# FPGA.net
KiCad netlist of a schematic drawn in Altium Designer
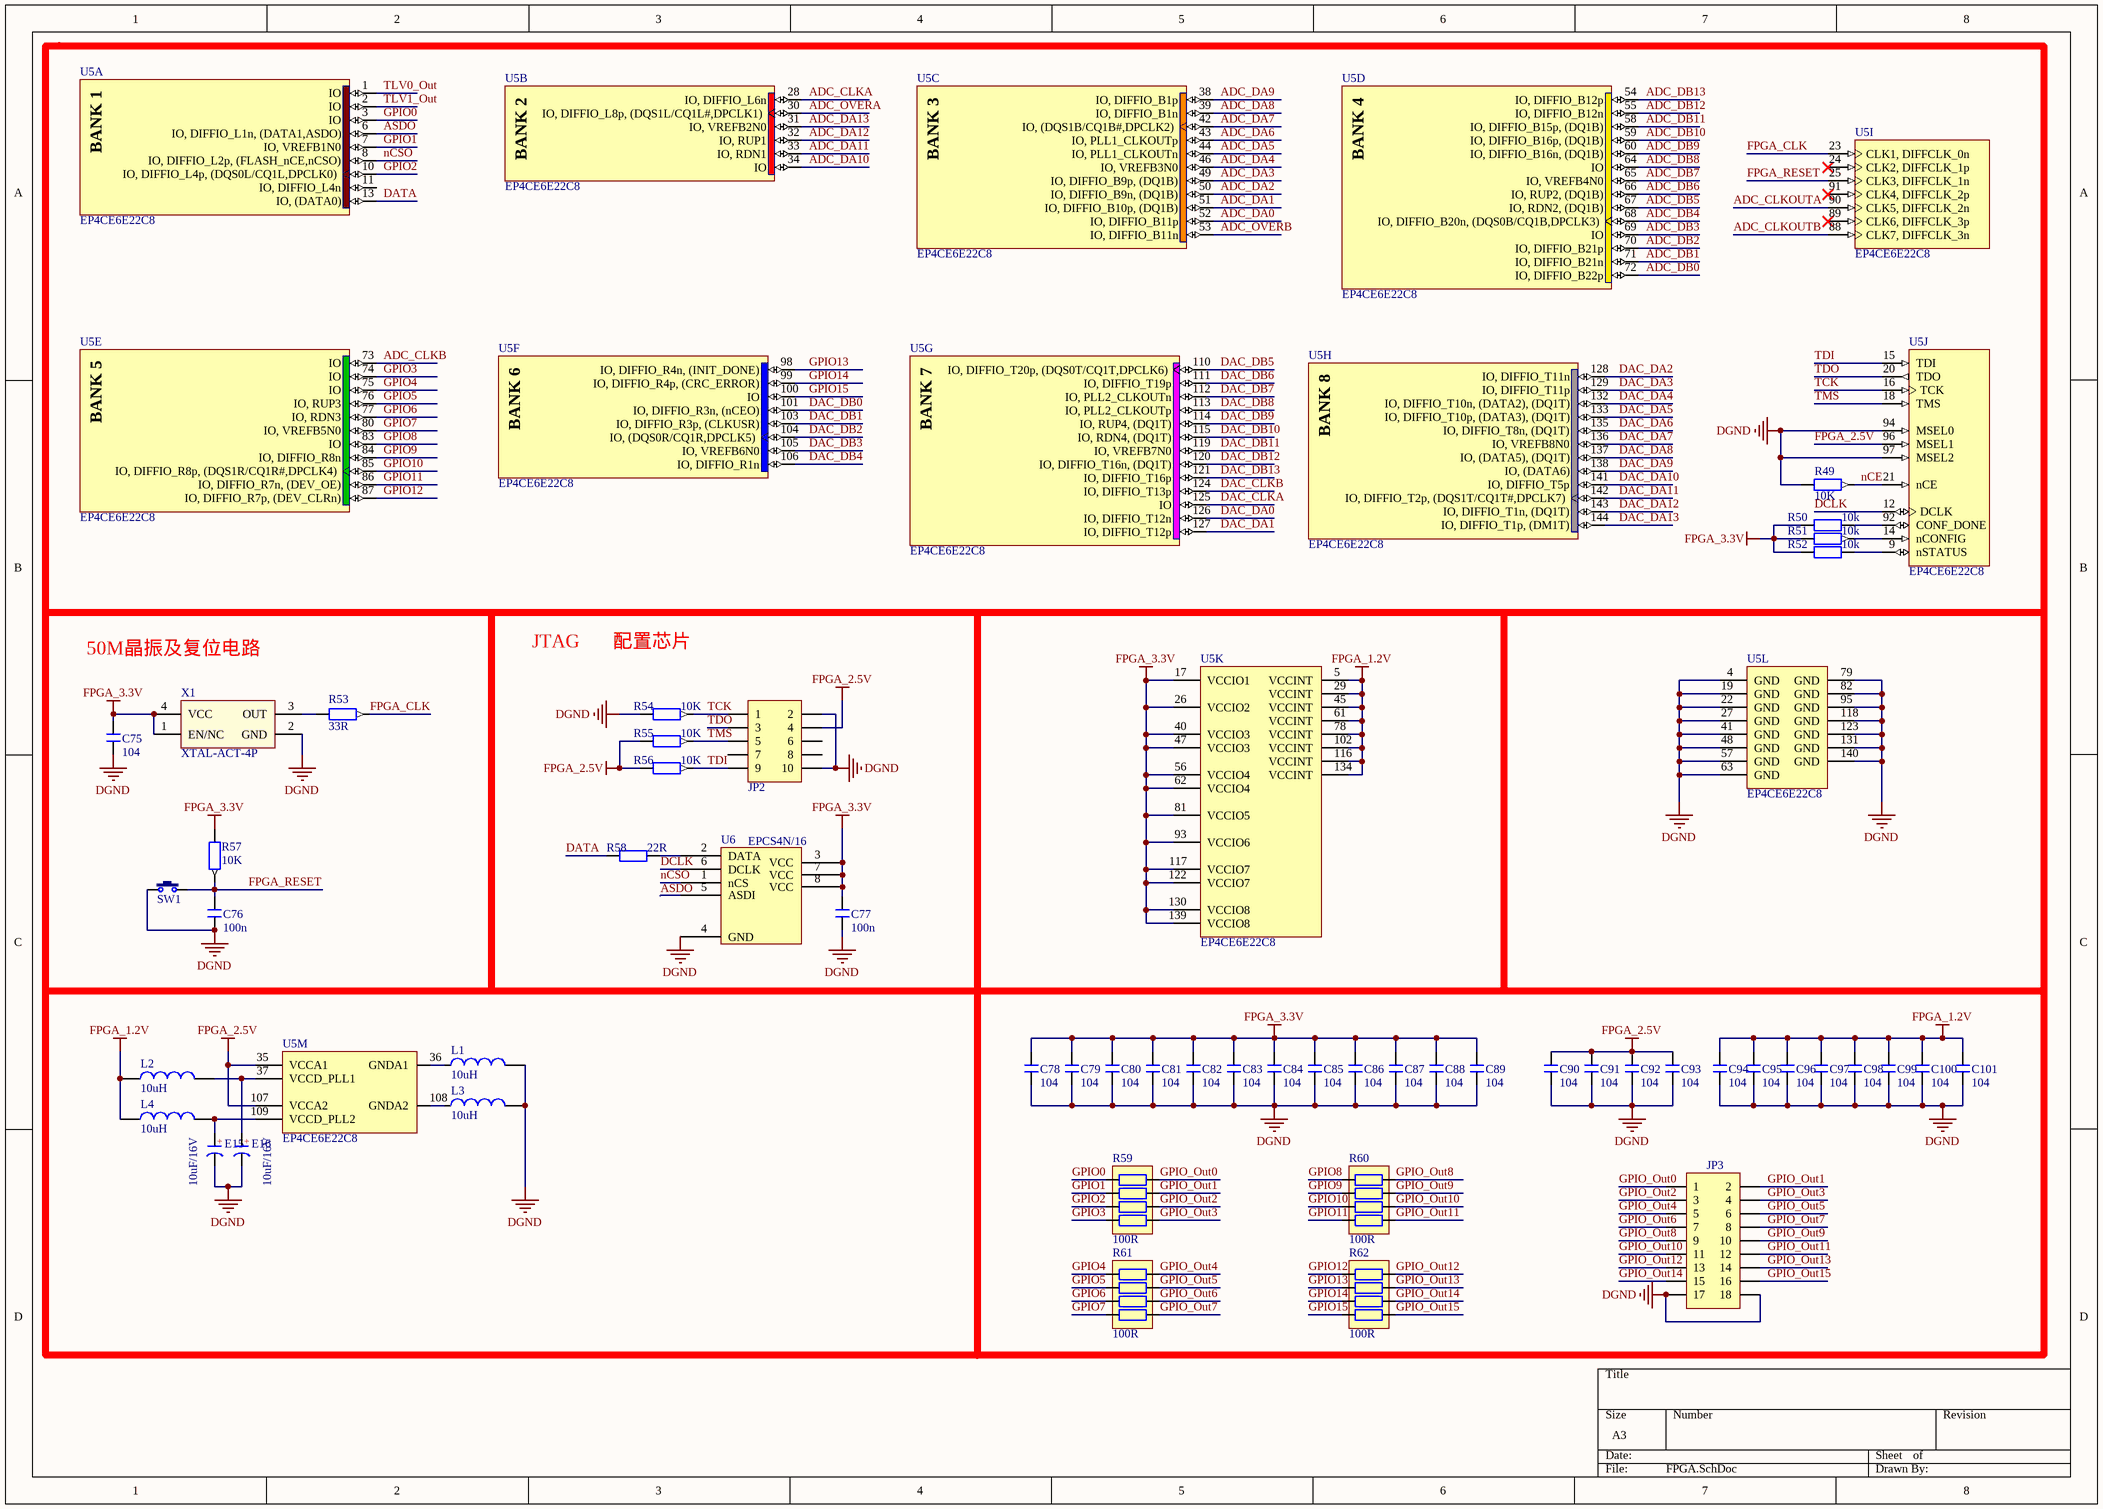
[diagram p0: FPGA.SchDoc]

(export (version "E")
  (design (tool "Eeschema 10.0.6"))
  (components
    (comp (ref "C75")
      (value "104")
      (footprint "C 0805_M")
      (description "无极性贴片电容")
      (fields (field (name "版权归属") "源创客"))
      (libsource (lib "3.1   - 电阻-电容-电感") (part "C"))
    )
    (comp (ref "C76")
      (value "100n")
      (footprint "C 0805_M")
      (description "无极性贴片电容")
      (fields (field (name "版权归属") "源创客"))
      (libsource (lib "3.1   - 电阻-电容-电感") (part "C"))
    )
    (comp (ref "C77")
      (value "100n")
      (footprint "C 0805_M")
      (description "无极性贴片电容")
      (fields (field (name "版权归属") "源创客"))
      (libsource (lib "3.1   - 电阻-电容-电感") (part "C"))
    )
    (comp (ref "C78")
      (value "104")
      (footprint "C 0805_M")
      (description "无极性贴片电容")
      (fields (field (name "版权归属") "源创客"))
      (libsource (lib "3.1   - 电阻-电容-电感") (part "C"))
    )
    (comp (ref "C79")
      (value "104")
      (footprint "C 0805_M")
      (description "无极性贴片电容")
      (fields (field (name "版权归属") "源创客"))
      (libsource (lib "3.1   - 电阻-电容-电感") (part "C"))
    )
    (comp (ref "C80")
      (value "104")
      (footprint "C 0805_M")
      (description "无极性贴片电容")
      (fields (field (name "版权归属") "源创客"))
      (libsource (lib "3.1   - 电阻-电容-电感") (part "C"))
    )
    (comp (ref "C81")
      (value "104")
      (footprint "C 0805_M")
      (description "无极性贴片电容")
      (fields (field (name "版权归属") "源创客"))
      (libsource (lib "3.1   - 电阻-电容-电感") (part "C"))
    )
    (comp (ref "C82")
      (value "104")
      (footprint "C 0805_M")
      (description "无极性贴片电容")
      (fields (field (name "版权归属") "源创客"))
      (libsource (lib "3.1   - 电阻-电容-电感") (part "C"))
    )
    (comp (ref "C83")
      (value "104")
      (footprint "C 0805_M")
      (description "无极性贴片电容")
      (fields (field (name "版权归属") "源创客"))
      (libsource (lib "3.1   - 电阻-电容-电感") (part "C"))
    )
    (comp (ref "C84")
      (value "104")
      (footprint "C 0805_M")
      (description "无极性贴片电容")
      (fields (field (name "版权归属") "源创客"))
      (libsource (lib "3.1   - 电阻-电容-电感") (part "C"))
    )
    (comp (ref "C85")
      (value "104")
      (footprint "C 0805_M")
      (description "无极性贴片电容")
      (fields (field (name "版权归属") "源创客"))
      (libsource (lib "3.1   - 电阻-电容-电感") (part "C"))
    )
    (comp (ref "C86")
      (value "104")
      (footprint "C 0805_M")
      (description "无极性贴片电容")
      (fields (field (name "版权归属") "源创客"))
      (libsource (lib "3.1   - 电阻-电容-电感") (part "C"))
    )
    (comp (ref "C87")
      (value "104")
      (footprint "C 0805_M")
      (description "无极性贴片电容")
      (fields (field (name "版权归属") "源创客"))
      (libsource (lib "3.1   - 电阻-电容-电感") (part "C"))
    )
    (comp (ref "C88")
      (value "104")
      (footprint "C 0805_M")
      (description "无极性贴片电容")
      (fields (field (name "版权归属") "源创客"))
      (libsource (lib "3.1   - 电阻-电容-电感") (part "C"))
    )
    (comp (ref "C89")
      (value "104")
      (footprint "C 0805_M")
      (description "无极性贴片电容")
      (fields (field (name "版权归属") "源创客"))
      (libsource (lib "3.1   - 电阻-电容-电感") (part "C"))
    )
    (comp (ref "C90")
      (value "104")
      (footprint "C 0805_M")
      (description "无极性贴片电容")
      (fields (field (name "版权归属") "源创客"))
      (libsource (lib "3.1   - 电阻-电容-电感") (part "C"))
    )
    (comp (ref "C91")
      (value "104")
      (footprint "C 0805_M")
      (description "无极性贴片电容")
      (fields (field (name "版权归属") "源创客"))
      (libsource (lib "3.1   - 电阻-电容-电感") (part "C"))
    )
    (comp (ref "C92")
      (value "104")
      (footprint "C 0805_M")
      (description "无极性贴片电容")
      (fields (field (name "版权归属") "源创客"))
      (libsource (lib "3.1   - 电阻-电容-电感") (part "C"))
    )
    (comp (ref "C93")
      (value "104")
      (footprint "C 0805_M")
      (description "无极性贴片电容")
      (fields (field (name "版权归属") "源创客"))
      (libsource (lib "3.1   - 电阻-电容-电感") (part "C"))
    )
    (comp (ref "C94")
      (value "104")
      (footprint "C 0805_M")
      (description "无极性贴片电容")
      (fields (field (name "版权归属") "源创客"))
      (libsource (lib "3.1   - 电阻-电容-电感") (part "C"))
    )
    (comp (ref "C95")
      (value "104")
      (footprint "C 0805_M")
      (description "无极性贴片电容")
      (fields (field (name "版权归属") "源创客"))
      (libsource (lib "3.1   - 电阻-电容-电感") (part "C"))
    )
    (comp (ref "C96")
      (value "104")
      (footprint "C 0805_M")
      (description "无极性贴片电容")
      (fields (field (name "版权归属") "源创客"))
      (libsource (lib "3.1   - 电阻-电容-电感") (part "C"))
    )
    (comp (ref "C97")
      (value "104")
      (footprint "C 0805_M")
      (description "无极性贴片电容")
      (fields (field (name "版权归属") "源创客"))
      (libsource (lib "3.1   - 电阻-电容-电感") (part "C"))
    )
    (comp (ref "C98")
      (value "104")
      (footprint "C 0805_M")
      (description "无极性贴片电容")
      (fields (field (name "版权归属") "源创客"))
      (libsource (lib "3.1   - 电阻-电容-电感") (part "C"))
    )
    (comp (ref "C99")
      (value "104")
      (footprint "C 0805_M")
      (description "无极性贴片电容")
      (fields (field (name "版权归属") "源创客"))
      (libsource (lib "3.1   - 电阻-电容-电感") (part "C"))
    )
    (comp (ref "C100")
      (value "104")
      (footprint "C 0805_M")
      (description "无极性贴片电容")
      (fields (field (name "版权归属") "源创客"))
      (libsource (lib "3.1   - 电阻-电容-电感") (part "C"))
    )
    (comp (ref "C101")
      (value "104")
      (footprint "C 0805_M")
      (description "无极性贴片电容")
      (fields (field (name "版权归属") "源创客"))
      (libsource (lib "3.1   - 电阻-电容-电感") (part "C"))
    )
    (comp (ref "E15")
      (value "10uF/16V")
      (footprint "C 1210_M")
      (description "直插电解电容")
      (fields (field (name "版权归属") "源创客"))
      (libsource (lib "3.1   - 电阻-电容-电感") (part "C-CAP"))
    )
    (comp (ref "E16")
      (value "10uF/16V")
      (footprint "C 1210_M")
      (description "直插电解电容")
      (fields (field (name "版权归属") "源创客"))
      (libsource (lib "3.1   - 电阻-电容-电感") (part "C-CAP"))
    )
    (comp (ref "JP2")
      (value "Header 5X2")
      (footprint "IDC2.54-LI-2x5P")
      (description "5*2P接插件")
      (fields (field (name "版权归属") "源创客"))
      (libsource (lib "4.5   - 接插件-脚距2.54") (part "Header 5X2"))
    )
    (comp (ref "JP3")
      (value "Header 9X2")
      (footprint "HDR2.54-LI-2x9P")
      (description "9*2P接插件")
      (fields (field (name "版权归属") "源创客"))
      (libsource (lib "4.5   - 接插件-脚距2.54") (part "Header 9X2"))
    )
    (comp (ref "L1")
      (value "10uH")
      (footprint "L 0805")
      (description "小功率贴片电感")
      (fields (field (name "版权归属") "源创客"))
      (libsource (lib "3.1   - 电阻-电容-电感") (part "L"))
    )
    (comp (ref "L2")
      (value "10uH")
      (footprint "L 0805")
      (description "小功率贴片电感")
      (fields (field (name "版权归属") "源创客"))
      (libsource (lib "3.1   - 电阻-电容-电感") (part "L"))
    )
    (comp (ref "L3")
      (value "10uH")
      (footprint "L 0805")
      (description "小功率贴片电感")
      (fields (field (name "版权归属") "源创客"))
      (libsource (lib "3.1   - 电阻-电容-电感") (part "L"))
    )
    (comp (ref "L4")
      (value "10uH")
      (footprint "L 0805")
      (description "小功率贴片电感")
      (fields (field (name "版权归属") "源创客"))
      (libsource (lib "3.1   - 电阻-电容-电感") (part "L"))
    )
    (comp (ref "R49")
      (value "10K")
      (footprint "R 0805_M")
      (description "Resistor")
      (fields (field (name "PUBLISHER") "Altium Limited"))
      (libsource (lib "Miscellaneous Devices") (part "Res2"))
    )
    (comp (ref "R50")
      (value "10k")
      (footprint "R 0805_M")
      (description "贴片电阻")
      (fields (field (name "版权归属") "源创客"))
      (libsource (lib "3.1   - 电阻-电容-电感") (part "R"))
    )
    (comp (ref "R51")
      (value "10k")
      (footprint "R 0805_M")
      (description "贴片电阻")
      (fields (field (name "版权归属") "源创客"))
      (libsource (lib "3.1   - 电阻-电容-电感") (part "R"))
    )
    (comp (ref "R52")
      (value "10k")
      (footprint "R 0805_M")
      (description "贴片电阻")
      (fields (field (name "版权归属") "源创客"))
      (libsource (lib "3.1   - 电阻-电容-电感") (part "R"))
    )
    (comp (ref "R53")
      (value "33R")
      (footprint "R 0805_M")
      (description "贴片电阻")
      (fields (field (name "版权归属") "源创客"))
      (libsource (lib "3.1   - 电阻-电容-电感") (part "R"))
    )
    (comp (ref "R54")
      (value "10K")
      (footprint "R 0805_M")
      (description "贴片电阻")
      (fields (field (name "版权归属") "源创客"))
      (libsource (lib "3.1   - 电阻-电容-电感") (part "R"))
    )
    (comp (ref "R55")
      (value "10K")
      (footprint "R 0805_M")
      (description "贴片电阻")
      (fields (field (name "版权归属") "源创客"))
      (libsource (lib "3.1   - 电阻-电容-电感") (part "R"))
    )
    (comp (ref "R56")
      (value "10K")
      (footprint "R 0805_M")
      (description "贴片电阻")
      (fields (field (name "版权归属") "源创客"))
      (libsource (lib "3.1   - 电阻-电容-电感") (part "R"))
    )
    (comp (ref "R57")
      (value "10K")
      (footprint "R 0805_M")
      (description "贴片电阻")
      (fields (field (name "版权归属") "源创客"))
      (libsource (lib "3.1   - 电阻-电容-电感") (part "R"))
    )
    (comp (ref "R58")
      (value "22R")
      (footprint "R 0805_M")
      (description "贴片电阻")
      (fields (field (name "版权归属") "源创客"))
      (libsource (lib "3.1   - 电阻-电容-电感") (part "R"))
    )
    (comp (ref "R59")
      (value "100R")
      (footprint "RCA-8P4R-0603")
      (description "贴片网络排阻")
      (fields (field (name "版权归属") "源创客"))
      (libsource (lib "") (part "R-8P4R_1"))
    )
    (comp (ref "R60")
      (value "100R")
      (footprint "RCA-8P4R-0603")
      (description "贴片网络排阻")
      (fields (field (name "版权归属") "源创客"))
      (libsource (lib "") (part "R-8P4R_1"))
    )
    (comp (ref "R61")
      (value "100R")
      (footprint "RCA-8P4R-0603")
      (description "贴片网络排阻")
      (fields (field (name "版权归属") "源创客"))
      (libsource (lib "3.1   - 电阻-电容-电感") (part "R-8P4R"))
    )
    (comp (ref "R62")
      (value "100R")
      (footprint "RCA-8P4R-0603")
      (description "贴片网络排阻")
      (fields (field (name "版权归属") "源创客"))
      (libsource (lib "") (part "R-8P4R_1"))
    )
    (comp (ref "SW1")
      (value "3x6x5")
      (footprint "TSW SMD-3*6*2.5")
      (description "3x6轻触开关")
      (fields (field (name "版权归属") "源创客"))
      (libsource (lib "5.1   - 按键-开关") (part "TSW 3x6"))
    )
    (comp (ref "U5")
      (value "EP4CE6E22C8")
      (footprint "EQFP144_M")
      (description "Cyclone IV Family FPGA, 2V Core, 91 I/O Pins, 2 PLLs, 144-Pin QFP, Speed Grade 8, Commercial Grade")
      (fields (field (name "PUBLISHER") "Altium Limited"))
      (libsource (lib "Altera Cyclone IV E") (part "EP4CE6E22C8"))
    )
    (comp (ref "U6") (value "EPCS4N/16") (footprint "SOP8_M") (libsource (lib "M4") (part "EPCS1SI8")))
    (comp (ref "X1")
      (value "XTAL-ACT-4P")
      (footprint "OSC 7050-4P")
      (description "4脚有源晶振")
      (libsource (lib "晶振") (part "XTAL-ACT-4P"))
    )
  )
  (nets
    (net (code "1") (name "/ADC_CLKA") (class "Default")
      (node (ref "U5") (pin "28") (pinfunction "IO,_DIFFIO_L6n_28") (pintype "bidirectional"))
    )
    (net (code "2") (name "/ADC_CLKB") (class "Default")
      (node (ref "U5") (pin "73") (pinfunction "IO_73") (pintype "bidirectional"))
    )
    (net (code "3") (name "/ADC_CLKOUTA") (class "Default")
      (node (ref "U5") (pin "90") (pinfunction "CLK5,_DIFFCLK_2n_90") (pintype "input"))
    )
    (net (code "4") (name "/ADC_CLKOUTB") (class "Default")
      (node (ref "U5") (pin "88") (pinfunction "CLK7,_DIFFCLK_3n_88") (pintype "input"))
    )
    (net (code "5") (name "/ADC_DA0") (class "Default")
      (node (ref "U5") (pin "52") (pinfunction "IO,_DIFFIO_B11p_52") (pintype "bidirectional"))
    )
    (net (code "6") (name "/ADC_DA1") (class "Default")
      (node (ref "U5") (pin "51") (pinfunction "IO,_DIFFIO_B10p,_(DQ1B)_51") (pintype "bidirectional"))
    )
    (net (code "7") (name "/ADC_DA2") (class "Default")
      (node (ref "U5") (pin "50") (pinfunction "IO,_DIFFIO_B9n,_(DQ1B)_50") (pintype "bidirectional"))
    )
    (net (code "8") (name "/ADC_DA3") (class "Default")
      (node (ref "U5") (pin "49") (pinfunction "IO,_DIFFIO_B9p,_(DQ1B)_49") (pintype "bidirectional"))
    )
    (net (code "9") (name "/ADC_DA4") (class "Default")
      (node (ref "U5") (pin "46") (pinfunction "IO,_VREFB3N0_46") (pintype "bidirectional"))
    )
    (net (code "10") (name "/ADC_DA5") (class "Default")
      (node (ref "U5") (pin "44") (pinfunction "IO,_PLL1_CLKOUTn_44") (pintype "bidirectional"))
    )
    (net (code "11") (name "/ADC_DA6") (class "Default")
      (node (ref "U5") (pin "43") (pinfunction "IO,_PLL1_CLKOUTp_43") (pintype "bidirectional"))
    )
    (net (code "12") (name "/ADC_DA7") (class "Default")
      (node (ref "U5") (pin "42") (pinfunction "IO,_(DQS1B/CQ1B#,DPCLK2)_42") (pintype "bidirectional"))
    )
    (net (code "13") (name "/ADC_DA8") (class "Default")
      (node (ref "U5") (pin "39") (pinfunction "IO,_DIFFIO_B1n_39") (pintype "bidirectional"))
    )
    (net (code "14") (name "/ADC_DA9") (class "Default")
      (node (ref "U5") (pin "38") (pinfunction "IO,_DIFFIO_B1p_38") (pintype "bidirectional"))
    )
    (net (code "15") (name "/ADC_DA10") (class "Default")
      (node (ref "U5") (pin "34") (pinfunction "IO_34") (pintype "bidirectional"))
    )
    (net (code "16") (name "/ADC_DA11") (class "Default")
      (node (ref "U5") (pin "33") (pinfunction "IO,_RDN1_33") (pintype "bidirectional"))
    )
    (net (code "17") (name "/ADC_DA12") (class "Default")
      (node (ref "U5") (pin "32") (pinfunction "IO,_RUP1_32") (pintype "bidirectional"))
    )
    (net (code "18") (name "/ADC_DA13") (class "Default")
      (node (ref "U5") (pin "31") (pinfunction "IO,_VREFB2N0_31") (pintype "bidirectional"))
    )
    (net (code "19") (name "/ADC_DB0") (class "Default")
      (node (ref "U5") (pin "72") (pinfunction "IO,_DIFFIO_B22p_72") (pintype "bidirectional"))
    )
    (net (code "20") (name "/ADC_DB1") (class "Default")
      (node (ref "U5") (pin "71") (pinfunction "IO,_DIFFIO_B21n_71") (pintype "bidirectional"))
    )
    (net (code "21") (name "/ADC_DB2") (class "Default")
      (node (ref "U5") (pin "70") (pinfunction "IO,_DIFFIO_B21p_70") (pintype "bidirectional"))
    )
    (net (code "22") (name "/ADC_DB3") (class "Default")
      (node (ref "U5") (pin "69") (pinfunction "IO_69") (pintype "bidirectional"))
    )
    (net (code "23") (name "/ADC_DB4") (class "Default")
      (node (ref "U5") (pin "68") (pinfunction "IO,_DIFFIO_B20n,_(DQS0B/CQ1B,DPCLK3)_68") (pintype "bidirectional"))
    )
    (net (code "24") (name "/ADC_DB5") (class "Default")
      (node (ref "U5") (pin "67") (pinfunction "IO,_RDN2,_(DQ1B)_67") (pintype "bidirectional"))
    )
    (net (code "25") (name "/ADC_DB6") (class "Default")
      (node (ref "U5") (pin "66") (pinfunction "IO,_RUP2,_(DQ1B)_66") (pintype "bidirectional"))
    )
    (net (code "26") (name "/ADC_DB7") (class "Default")
      (node (ref "U5") (pin "65") (pinfunction "IO,_VREFB4N0_65") (pintype "bidirectional"))
    )
    (net (code "27") (name "/ADC_DB8") (class "Default")
      (node (ref "U5") (pin "64") (pinfunction "IO_64") (pintype "bidirectional"))
    )
    (net (code "28") (name "/ADC_DB9") (class "Default")
      (node (ref "U5") (pin "60") (pinfunction "IO,_DIFFIO_B16n,_(DQ1B)_60") (pintype "bidirectional"))
    )
    (net (code "29") (name "/ADC_DB10") (class "Default")
      (node (ref "U5") (pin "59") (pinfunction "IO,_DIFFIO_B16p,_(DQ1B)_59") (pintype "bidirectional"))
    )
    (net (code "30") (name "/ADC_DB11") (class "Default")
      (node (ref "U5") (pin "58") (pinfunction "IO,_DIFFIO_B15p,_(DQ1B)_58") (pintype "bidirectional"))
    )
    (net (code "31") (name "/ADC_DB12") (class "Default")
      (node (ref "U5") (pin "55") (pinfunction "IO,_DIFFIO_B12n_55") (pintype "bidirectional"))
    )
    (net (code "32") (name "/ADC_DB13") (class "Default")
      (node (ref "U5") (pin "54") (pinfunction "IO,_DIFFIO_B12p_54") (pintype "bidirectional"))
    )
    (net (code "33") (name "/ADC_OVERA") (class "Default")
      (node (ref "U5") (pin "30") (pinfunction "IO,_DIFFIO_L8p,_(DQS1L/CQ1L#,DPCLK1)_30") (pintype "bidirectional"))
    )
    (net (code "34") (name "/ADC_OVERB") (class "Default")
      (node (ref "U5") (pin "53") (pinfunction "IO,_DIFFIO_B11n_53") (pintype "bidirectional"))
    )
    (net (code "35") (name "/ASDO") (class "Default")
      (node (ref "U5") (pin "6") (pinfunction "IO,_DIFFIO_L1n,_(DATA1,ASDO)_6") (pintype "bidirectional"))
      (node (ref "U6") (pin "5") (pinfunction "ASDI_5") (pintype "passive"))
    )
    (net (code "36") (name "/DAC_CLKA") (class "Default")
      (node (ref "U5") (pin "125") (pinfunction "IO_125") (pintype "bidirectional"))
    )
    (net (code "37") (name "/DAC_CLKB") (class "Default")
      (node (ref "U5") (pin "124") (pinfunction "IO,_DIFFIO_T13p_124") (pintype "bidirectional"))
    )
    (net (code "38") (name "/DAC_DA0") (class "Default")
      (node (ref "U5") (pin "126") (pinfunction "IO,_DIFFIO_T12n_126") (pintype "bidirectional"))
    )
    (net (code "39") (name "/DAC_DA1") (class "Default")
      (node (ref "U5") (pin "127") (pinfunction "IO,_DIFFIO_T12p_127") (pintype "bidirectional"))
    )
    (net (code "40") (name "/DAC_DA2") (class "Default")
      (node (ref "U5") (pin "128") (pinfunction "IO,_DIFFIO_T11n_128") (pintype "bidirectional"))
    )
    (net (code "41") (name "/DAC_DA3") (class "Default")
      (node (ref "U5") (pin "129") (pinfunction "IO,_DIFFIO_T11p_129") (pintype "bidirectional"))
    )
    (net (code "42") (name "/DAC_DA4") (class "Default")
      (node (ref "U5") (pin "132") (pinfunction "IO,_DIFFIO_T10n,_(DATA2),_(DQ1T)_132") (pintype "bidirectional"))
    )
    (net (code "43") (name "/DAC_DA5") (class "Default")
      (node (ref "U5") (pin "133") (pinfunction "IO,_DIFFIO_T10p,_(DATA3),_(DQ1T)_133") (pintype "bidirectional"))
    )
    (net (code "44") (name "/DAC_DA6") (class "Default")
      (node (ref "U5") (pin "135") (pinfunction "IO,_DIFFIO_T8n,_(DQ1T)_135") (pintype "bidirectional"))
    )
    (net (code "45") (name "/DAC_DA7") (class "Default")
      (node (ref "U5") (pin "136") (pinfunction "IO,_VREFB8N0_136") (pintype "bidirectional"))
    )
    (net (code "46") (name "/DAC_DA8") (class "Default")
      (node (ref "U5") (pin "137") (pinfunction "IO,_(DATA5),_(DQ1T)_137") (pintype "bidirectional"))
    )
    (net (code "47") (name "/DAC_DA9") (class "Default")
      (node (ref "U5") (pin "138") (pinfunction "IO,_(DATA6)_138") (pintype "bidirectional"))
    )
    (net (code "48") (name "/DAC_DA10") (class "Default")
      (node (ref "U5") (pin "141") (pinfunction "IO,_DIFFIO_T5p_141") (pintype "bidirectional"))
    )
    (net (code "49") (name "/DAC_DA11") (class "Default")
      (node (ref "U5") (pin "142") (pinfunction "IO,_DIFFIO_T2p,_(DQS1T/CQ1T#,DPCLK7)_142") (pintype "bidirectional"))
    )
    (net (code "50") (name "/DAC_DA12") (class "Default")
      (node (ref "U5") (pin "143") (pinfunction "IO,_DIFFIO_T1n,_(DQ1T)_143") (pintype "bidirectional"))
    )
    (net (code "51") (name "/DAC_DA13") (class "Default")
      (node (ref "U5") (pin "144") (pinfunction "IO,_DIFFIO_T1p,_(DM1T)_144") (pintype "bidirectional"))
    )
    (net (code "52") (name "/DAC_DB0") (class "Default")
      (node (ref "U5") (pin "101") (pinfunction "IO,_DIFFIO_R3n,_(nCEO)_101") (pintype "bidirectional"))
    )
    (net (code "53") (name "/DAC_DB1") (class "Default")
      (node (ref "U5") (pin "103") (pinfunction "IO,_DIFFIO_R3p,_(CLKUSR)_103") (pintype "bidirectional"))
    )
    (net (code "54") (name "/DAC_DB2") (class "Default")
      (node (ref "U5") (pin "104") (pinfunction "IO,_(DQS0R/CQ1R,DPCLK5)_104") (pintype "bidirectional"))
    )
    (net (code "55") (name "/DAC_DB3") (class "Default")
      (node (ref "U5") (pin "105") (pinfunction "IO,_VREFB6N0_105") (pintype "bidirectional"))
    )
    (net (code "56") (name "/DAC_DB4") (class "Default")
      (node (ref "U5") (pin "106") (pinfunction "IO,_DIFFIO_R1n_106") (pintype "bidirectional"))
    )
    (net (code "57") (name "/DAC_DB5") (class "Default")
      (node (ref "U5") (pin "110") (pinfunction "IO,_DIFFIO_T20p,_(DQS0T/CQ1T,DPCLK6)_110") (pintype "bidirectional"))
    )
    (net (code "58") (name "/DAC_DB6") (class "Default")
      (node (ref "U5") (pin "111") (pinfunction "IO,_DIFFIO_T19p_111") (pintype "bidirectional"))
    )
    (net (code "59") (name "/DAC_DB7") (class "Default")
      (node (ref "U5") (pin "112") (pinfunction "IO,_PLL2_CLKOUTn_112") (pintype "bidirectional"))
    )
    (net (code "60") (name "/DAC_DB8") (class "Default")
      (node (ref "U5") (pin "113") (pinfunction "IO,_PLL2_CLKOUTp_113") (pintype "bidirectional"))
    )
    (net (code "61") (name "/DAC_DB9") (class "Default")
      (node (ref "U5") (pin "114") (pinfunction "IO,_RUP4,_(DQ1T)_114") (pintype "bidirectional"))
    )
    (net (code "62") (name "/DAC_DB10") (class "Default")
      (node (ref "U5") (pin "115") (pinfunction "IO,_RDN4,_(DQ1T)_115") (pintype "bidirectional"))
    )
    (net (code "63") (name "/DAC_DB11") (class "Default")
      (node (ref "U5") (pin "119") (pinfunction "IO,_VREFB7N0_119") (pintype "bidirectional"))
    )
    (net (code "64") (name "/DAC_DB12") (class "Default")
      (node (ref "U5") (pin "120") (pinfunction "IO,_DIFFIO_T16n,_(DQ1T)_120") (pintype "bidirectional"))
    )
    (net (code "65") (name "/DAC_DB13") (class "Default")
      (node (ref "U5") (pin "121") (pinfunction "IO,_DIFFIO_T16p_121") (pintype "bidirectional"))
    )
    (net (code "66") (name "/DATA") (class "Default")
      (node (ref "R58") (pin "2") (pinfunction "2_2") (pintype "output"))
      (node (ref "U5") (pin "13") (pinfunction "IO,_(DATA0)_13") (pintype "bidirectional"))
    )
    (net (code "67") (name "/DCLK") (class "Default")
      (node (ref "U5") (pin "12") (pinfunction "DCLK_12") (pintype "bidirectional"))
      (node (ref "U6") (pin "6") (pinfunction "DCLK_6") (pintype "passive"))
    )
    (net (code "68") (name "/FPGA_CLK") (class "Default")
      (node (ref "R53") (pin "2") (pinfunction "2_2") (pintype "output"))
      (node (ref "U5") (pin "23") (pinfunction "CLK1,_DIFFCLK_0n_23") (pintype "input"))
    )
    (net (code "69") (name "/FPGA_RESET") (class "Default")
      (node (ref "C76") (pin "2") (pinfunction "2_2") (pintype "passive"))
      (node (ref "R57") (pin "1") (pinfunction "1_1") (pintype "passive"))
      (node (ref "SW1") (pin "2") (pinfunction "2_2") (pintype "passive"))
      (node (ref "U5") (pin "25") (pinfunction "CLK3,_DIFFCLK_1n_25") (pintype "input"))
    )
    (net (code "70") (name "/GPIO0") (class "Default")
      (node (ref "R59") (pin "8") (pinfunction "8_8") (pintype "passive"))
      (node (ref "U5") (pin "3") (pinfunction "IO_3") (pintype "bidirectional"))
    )
    (net (code "71") (name "/GPIO1") (class "Default")
      (node (ref "R59") (pin "7") (pinfunction "7_7") (pintype "passive"))
      (node (ref "U5") (pin "7") (pinfunction "IO,_VREFB1N0_7") (pintype "bidirectional"))
    )
    (net (code "72") (name "/GPIO2") (class "Default")
      (node (ref "R59") (pin "6") (pinfunction "6_6") (pintype "passive"))
      (node (ref "U5") (pin "10") (pinfunction "IO,_DIFFIO_L4p,_(DQS0L/CQ1L,DPCLK0)_10") (pintype "bidirectional"))
    )
    (net (code "73") (name "/GPIO3") (class "Default")
      (node (ref "R59") (pin "5") (pinfunction "5_5") (pintype "passive"))
      (node (ref "U5") (pin "74") (pinfunction "IO_74") (pintype "bidirectional"))
    )
    (net (code "74") (name "/GPIO4") (class "Default")
      (node (ref "R61") (pin "4") (pinfunction "4_4") (pintype "passive"))
      (node (ref "U5") (pin "75") (pinfunction "IO_75") (pintype "bidirectional"))
    )
    (net (code "75") (name "/GPIO5") (class "Default")
      (node (ref "R61") (pin "3") (pinfunction "3_3") (pintype "passive"))
      (node (ref "U5") (pin "76") (pinfunction "IO,_RUP3_76") (pintype "bidirectional"))
    )
    (net (code "76") (name "/GPIO6") (class "Default")
      (node (ref "R61") (pin "2") (pinfunction "2_2") (pintype "passive"))
      (node (ref "U5") (pin "77") (pinfunction "IO,_RDN3_77") (pintype "bidirectional"))
    )
    (net (code "77") (name "/GPIO7") (class "Default")
      (node (ref "R61") (pin "1") (pinfunction "1_1") (pintype "passive"))
      (node (ref "U5") (pin "80") (pinfunction "IO,_VREFB5N0_80") (pintype "bidirectional"))
    )
    (net (code "78") (name "/GPIO8") (class "Default")
      (node (ref "R60") (pin "8") (pinfunction "8_8") (pintype "passive"))
      (node (ref "U5") (pin "83") (pinfunction "IO_83") (pintype "bidirectional"))
    )
    (net (code "79") (name "/GPIO9") (class "Default")
      (node (ref "R60") (pin "7") (pinfunction "7_7") (pintype "passive"))
      (node (ref "U5") (pin "84") (pinfunction "IO,_DIFFIO_R8n_84") (pintype "bidirectional"))
    )
    (net (code "80") (name "/GPIO10") (class "Default")
      (node (ref "R60") (pin "6") (pinfunction "6_6") (pintype "passive"))
      (node (ref "U5") (pin "85") (pinfunction "IO,_DIFFIO_R8p,_(DQS1R/CQ1R#,DPCLK4)_85") (pintype "bidirectional"))
    )
    (net (code "81") (name "/GPIO11") (class "Default")
      (node (ref "R60") (pin "5") (pinfunction "5_5") (pintype "passive"))
      (node (ref "U5") (pin "86") (pinfunction "IO,_DIFFIO_R7n,_(DEV_OE)_86") (pintype "bidirectional"))
    )
    (net (code "82") (name "/GPIO12") (class "Default")
      (node (ref "R62") (pin "8") (pinfunction "8_8") (pintype "passive"))
      (node (ref "U5") (pin "87") (pinfunction "IO,_DIFFIO_R7p,_(DEV_CLRn)_87") (pintype "bidirectional"))
    )
    (net (code "83") (name "/GPIO13") (class "Default")
      (node (ref "R62") (pin "7") (pinfunction "7_7") (pintype "passive"))
      (node (ref "U5") (pin "98") (pinfunction "IO,_DIFFIO_R4n,_(INIT_DONE)_98") (pintype "bidirectional"))
    )
    (net (code "84") (name "/GPIO14") (class "Default")
      (node (ref "R62") (pin "6") (pinfunction "6_6") (pintype "passive"))
      (node (ref "U5") (pin "99") (pinfunction "IO,_DIFFIO_R4p,_(CRC_ERROR)_99") (pintype "bidirectional"))
    )
    (net (code "85") (name "/GPIO15") (class "Default")
      (node (ref "R62") (pin "5") (pinfunction "5_5") (pintype "passive"))
      (node (ref "U5") (pin "100") (pinfunction "IO_100") (pintype "bidirectional"))
    )
    (net (code "86") (name "/GPIO_Out0") (class "Default")
      (node (ref "JP3") (pin "1") (pinfunction "1_1") (pintype "passive"))
      (node (ref "R59") (pin "1") (pinfunction "1_1") (pintype "passive"))
    )
    (net (code "87") (name "/GPIO_Out1") (class "Default")
      (node (ref "JP3") (pin "2") (pinfunction "2_2") (pintype "passive"))
      (node (ref "R59") (pin "2") (pinfunction "2_2") (pintype "passive"))
    )
    (net (code "88") (name "/GPIO_Out2") (class "Default")
      (node (ref "JP3") (pin "3") (pinfunction "3_3") (pintype "passive"))
      (node (ref "R59") (pin "3") (pinfunction "3_3") (pintype "passive"))
    )
    (net (code "89") (name "/GPIO_Out3") (class "Default")
      (node (ref "JP3") (pin "4") (pinfunction "4_4") (pintype "passive"))
      (node (ref "R59") (pin "4") (pinfunction "4_4") (pintype "passive"))
    )
    (net (code "90") (name "/GPIO_Out4") (class "Default")
      (node (ref "JP3") (pin "5") (pinfunction "5_5") (pintype "passive"))
      (node (ref "R61") (pin "5") (pinfunction "5_5") (pintype "passive"))
    )
    (net (code "91") (name "/GPIO_Out5") (class "Default")
      (node (ref "JP3") (pin "6") (pinfunction "6_6") (pintype "passive"))
      (node (ref "R61") (pin "6") (pinfunction "6_6") (pintype "passive"))
    )
    (net (code "92") (name "/GPIO_Out6") (class "Default")
      (node (ref "JP3") (pin "7") (pinfunction "7_7") (pintype "passive"))
      (node (ref "R61") (pin "7") (pinfunction "7_7") (pintype "passive"))
    )
    (net (code "93") (name "/GPIO_Out7") (class "Default")
      (node (ref "JP3") (pin "8") (pinfunction "8_8") (pintype "passive"))
      (node (ref "R61") (pin "8") (pinfunction "8_8") (pintype "passive"))
    )
    (net (code "94") (name "/GPIO_Out8") (class "Default")
      (node (ref "JP3") (pin "9") (pinfunction "9_9") (pintype "passive"))
      (node (ref "R60") (pin "1") (pinfunction "1_1") (pintype "passive"))
    )
    (net (code "95") (name "/GPIO_Out9") (class "Default")
      (node (ref "JP3") (pin "10") (pinfunction "10_10") (pintype "passive"))
      (node (ref "R60") (pin "2") (pinfunction "2_2") (pintype "passive"))
    )
    (net (code "96") (name "/GPIO_Out10") (class "Default")
      (node (ref "JP3") (pin "11") (pinfunction "11_11") (pintype "passive"))
      (node (ref "R60") (pin "3") (pinfunction "3_3") (pintype "passive"))
    )
    (net (code "97") (name "/GPIO_Out11") (class "Default")
      (node (ref "JP3") (pin "12") (pinfunction "12_12") (pintype "passive"))
      (node (ref "R60") (pin "4") (pinfunction "4_4") (pintype "passive"))
    )
    (net (code "98") (name "/GPIO_Out12") (class "Default")
      (node (ref "JP3") (pin "13") (pinfunction "13_13") (pintype "passive"))
      (node (ref "R62") (pin "1") (pinfunction "1_1") (pintype "passive"))
    )
    (net (code "99") (name "/GPIO_Out13") (class "Default")
      (node (ref "JP3") (pin "14") (pinfunction "14_14") (pintype "passive"))
      (node (ref "R62") (pin "2") (pinfunction "2_2") (pintype "passive"))
    )
    (net (code "100") (name "/GPIO_Out14") (class "Default")
      (node (ref "JP3") (pin "15") (pinfunction "15_15") (pintype "passive"))
      (node (ref "R62") (pin "3") (pinfunction "3_3") (pintype "passive"))
    )
    (net (code "101") (name "/GPIO_Out15") (class "Default")
      (node (ref "JP3") (pin "16") (pinfunction "16_16") (pintype "passive"))
      (node (ref "R62") (pin "4") (pinfunction "4_4") (pintype "passive"))
    )
    (net (code "102") (name "/TCK") (class "Default")
      (node (ref "JP2") (pin "1") (pinfunction "1_1") (pintype "passive"))
      (node (ref "R54") (pin "1") (pinfunction "1_1") (pintype "passive"))
      (node (ref "U5") (pin "16") (pinfunction "TCK_16") (pintype "input"))
    )
    (net (code "103") (name "/TDI") (class "Default")
      (node (ref "JP2") (pin "9") (pinfunction "9_9") (pintype "passive"))
      (node (ref "R56") (pin "1") (pinfunction "1_1") (pintype "passive"))
      (node (ref "U5") (pin "15") (pinfunction "TDI_15") (pintype "input"))
    )
    (net (code "104") (name "/TDO") (class "Default")
      (node (ref "JP2") (pin "3") (pinfunction "3_3") (pintype "passive"))
      (node (ref "U5") (pin "20") (pinfunction "TDO_20") (pintype "output"))
    )
    (net (code "105") (name "/TLV0_Out") (class "Default")
      (node (ref "U5") (pin "1") (pinfunction "IO_1") (pintype "bidirectional"))
    )
    (net (code "106") (name "/TLV1_Out") (class "Default")
      (node (ref "U5") (pin "2") (pinfunction "IO_2") (pintype "bidirectional"))
    )
    (net (code "107") (name "/TMS") (class "Default")
      (node (ref "JP2") (pin "5") (pinfunction "5_5") (pintype "passive"))
      (node (ref "R55") (pin "1") (pinfunction "1_1") (pintype "passive"))
      (node (ref "U5") (pin "18") (pinfunction "TMS_18") (pintype "input"))
    )
    (net (code "108") (name "/nCE") (class "Default")
      (node (ref "R49") (pin "2") (pinfunction "2_2") (pintype "output"))
      (node (ref "U5") (pin "21") (pinfunction "nCE_21") (pintype "input"))
    )
    (net (code "109") (name "/nCSO") (class "Default")
      (node (ref "U5") (pin "8") (pinfunction "IO,_DIFFIO_L2p,_(FLASH_nCE,nCSO)_8") (pintype "bidirectional"))
      (node (ref "U6") (pin "1") (pinfunction "nCS_1") (pintype "passive"))
    )
    (net (code "110") (name "DGND") (class "Default")
      (node (ref "C100") (pin "1") (pinfunction "1_1") (pintype "passive"))
      (node (ref "C101") (pin "1") (pinfunction "1_1") (pintype "passive"))
      (node (ref "C75") (pin "1") (pinfunction "1_1") (pintype "passive"))
      (node (ref "C76") (pin "1") (pinfunction "1_1") (pintype "passive"))
      (node (ref "C77") (pin "1") (pinfunction "1_1") (pintype "passive"))
      (node (ref "C78") (pin "1") (pinfunction "1_1") (pintype "passive"))
      (node (ref "C79") (pin "1") (pinfunction "1_1") (pintype "passive"))
      (node (ref "C80") (pin "1") (pinfunction "1_1") (pintype "passive"))
      (node (ref "C81") (pin "1") (pinfunction "1_1") (pintype "passive"))
      (node (ref "C82") (pin "1") (pinfunction "1_1") (pintype "passive"))
      (node (ref "C83") (pin "1") (pinfunction "1_1") (pintype "passive"))
      (node (ref "C84") (pin "1") (pinfunction "1_1") (pintype "passive"))
      (node (ref "C85") (pin "1") (pinfunction "1_1") (pintype "passive"))
      (node (ref "C86") (pin "1") (pinfunction "1_1") (pintype "passive"))
      (node (ref "C87") (pin "1") (pinfunction "1_1") (pintype "passive"))
      (node (ref "C88") (pin "1") (pinfunction "1_1") (pintype "passive"))
      (node (ref "C89") (pin "1") (pinfunction "1_1") (pintype "passive"))
      (node (ref "C90") (pin "1") (pinfunction "1_1") (pintype "passive"))
      (node (ref "C91") (pin "1") (pinfunction "1_1") (pintype "passive"))
      (node (ref "C92") (pin "1") (pinfunction "1_1") (pintype "passive"))
      (node (ref "C93") (pin "1") (pinfunction "1_1") (pintype "passive"))
      (node (ref "C94") (pin "1") (pinfunction "1_1") (pintype "passive"))
      (node (ref "C95") (pin "1") (pinfunction "1_1") (pintype "passive"))
      (node (ref "C96") (pin "1") (pinfunction "1_1") (pintype "passive"))
      (node (ref "C97") (pin "1") (pinfunction "1_1") (pintype "passive"))
      (node (ref "C98") (pin "1") (pinfunction "1_1") (pintype "passive"))
      (node (ref "C99") (pin "1") (pinfunction "1_1") (pintype "passive"))
      (node (ref "E15") (pin "2") (pinfunction "K_2") (pintype "passive"))
      (node (ref "E16") (pin "2") (pinfunction "K_2") (pintype "passive"))
      (node (ref "JP2") (pin "10") (pinfunction "10_10") (pintype "passive"))
      (node (ref "JP2") (pin "2") (pinfunction "2_2") (pintype "passive"))
      (node (ref "JP3") (pin "17") (pinfunction "17_17") (pintype "passive"))
      (node (ref "JP3") (pin "18") (pinfunction "18_18") (pintype "passive"))
      (node (ref "L1") (pin "2") (pinfunction "2_2") (pintype "passive"))
      (node (ref "L3") (pin "2") (pinfunction "2_2") (pintype "passive"))
      (node (ref "R49") (pin "1") (pinfunction "1_1") (pintype "passive"))
      (node (ref "R54") (pin "2") (pinfunction "2_2") (pintype "output"))
      (node (ref "SW1") (pin "1") (pinfunction "1_1") (pintype "passive"))
      (node (ref "U5") (pin "118") (pinfunction "GND_118") (pintype "power_in"))
      (node (ref "U5") (pin "123") (pinfunction "GND_123") (pintype "power_in"))
      (node (ref "U5") (pin "131") (pinfunction "GND_131") (pintype "power_in"))
      (node (ref "U5") (pin "140") (pinfunction "GND_140") (pintype "power_in"))
      (node (ref "U5") (pin "19") (pinfunction "GND_19") (pintype "power_in"))
      (node (ref "U5") (pin "22") (pinfunction "GND_22") (pintype "power_in"))
      (node (ref "U5") (pin "27") (pinfunction "GND_27") (pintype "power_in"))
      (node (ref "U5") (pin "4") (pinfunction "GND_4") (pintype "power_in"))
      (node (ref "U5") (pin "41") (pinfunction "GND_41") (pintype "power_in"))
      (node (ref "U5") (pin "48") (pinfunction "GND_48") (pintype "power_in"))
      (node (ref "U5") (pin "57") (pinfunction "GND_57") (pintype "power_in"))
      (node (ref "U5") (pin "63") (pinfunction "GND_63") (pintype "power_in"))
      (node (ref "U5") (pin "79") (pinfunction "GND_79") (pintype "power_in"))
      (node (ref "U5") (pin "82") (pinfunction "GND_82") (pintype "power_in"))
      (node (ref "U5") (pin "94") (pinfunction "MSEL0_94") (pintype "input"))
      (node (ref "U5") (pin "95") (pinfunction "GND_95") (pintype "power_in"))
      (node (ref "U5") (pin "97") (pinfunction "MSEL2_97") (pintype "input"))
      (node (ref "U6") (pin "4") (pinfunction "GND_4") (pintype "passive"))
      (node (ref "X1") (pin "2") (pinfunction "GND_2") (pintype "passive"))
    )
    (net (code "111") (name "FPGA_1.2V") (class "Default")
      (node (ref "C100") (pin "2") (pinfunction "2_2") (pintype "passive"))
      (node (ref "C101") (pin "2") (pinfunction "2_2") (pintype "passive"))
      (node (ref "C94") (pin "2") (pinfunction "2_2") (pintype "passive"))
      (node (ref "C95") (pin "2") (pinfunction "2_2") (pintype "passive"))
      (node (ref "C96") (pin "2") (pinfunction "2_2") (pintype "passive"))
      (node (ref "C97") (pin "2") (pinfunction "2_2") (pintype "passive"))
      (node (ref "C98") (pin "2") (pinfunction "2_2") (pintype "passive"))
      (node (ref "C99") (pin "2") (pinfunction "2_2") (pintype "passive"))
      (node (ref "L2") (pin "1") (pinfunction "1_1") (pintype "passive"))
      (node (ref "L4") (pin "1") (pinfunction "1_1") (pintype "passive"))
      (node (ref "U5") (pin "102") (pinfunction "VCCINT_102") (pintype "power_in"))
      (node (ref "U5") (pin "116") (pinfunction "VCCINT_116") (pintype "power_in"))
      (node (ref "U5") (pin "134") (pinfunction "VCCINT_134") (pintype "power_in"))
      (node (ref "U5") (pin "29") (pinfunction "VCCINT_29") (pintype "power_in"))
      (node (ref "U5") (pin "45") (pinfunction "VCCINT_45") (pintype "power_in"))
      (node (ref "U5") (pin "5") (pinfunction "VCCINT_5") (pintype "power_in"))
      (node (ref "U5") (pin "61") (pinfunction "VCCINT_61") (pintype "power_in"))
      (node (ref "U5") (pin "78") (pinfunction "VCCINT_78") (pintype "power_in"))
    )
    (net (code "112") (name "FPGA_2.5V") (class "Default")
      (node (ref "C90") (pin "2") (pinfunction "2_2") (pintype "passive"))
      (node (ref "C91") (pin "2") (pinfunction "2_2") (pintype "passive"))
      (node (ref "C92") (pin "2") (pinfunction "2_2") (pintype "passive"))
      (node (ref "C93") (pin "2") (pinfunction "2_2") (pintype "passive"))
      (node (ref "JP2") (pin "4") (pinfunction "4_4") (pintype "passive"))
      (node (ref "R55") (pin "2") (pinfunction "2_2") (pintype "output"))
      (node (ref "R56") (pin "2") (pinfunction "2_2") (pintype "output"))
      (node (ref "U5") (pin "107") (pinfunction "VCCA2_107") (pintype "power_in"))
      (node (ref "U5") (pin "35") (pinfunction "VCCA1_35") (pintype "power_in"))
      (node (ref "U5") (pin "96") (pinfunction "MSEL1_96") (pintype "input"))
    )
    (net (code "113") (name "FPGA_3.3V") (class "Default")
      (node (ref "C75") (pin "2") (pinfunction "2_2") (pintype "passive"))
      (node (ref "C77") (pin "2") (pinfunction "2_2") (pintype "passive"))
      (node (ref "C78") (pin "2") (pinfunction "2_2") (pintype "passive"))
      (node (ref "C79") (pin "2") (pinfunction "2_2") (pintype "passive"))
      (node (ref "C80") (pin "2") (pinfunction "2_2") (pintype "passive"))
      (node (ref "C81") (pin "2") (pinfunction "2_2") (pintype "passive"))
      (node (ref "C82") (pin "2") (pinfunction "2_2") (pintype "passive"))
      (node (ref "C83") (pin "2") (pinfunction "2_2") (pintype "passive"))
      (node (ref "C84") (pin "2") (pinfunction "2_2") (pintype "passive"))
      (node (ref "C85") (pin "2") (pinfunction "2_2") (pintype "passive"))
      (node (ref "C86") (pin "2") (pinfunction "2_2") (pintype "passive"))
      (node (ref "C87") (pin "2") (pinfunction "2_2") (pintype "passive"))
      (node (ref "C88") (pin "2") (pinfunction "2_2") (pintype "passive"))
      (node (ref "C89") (pin "2") (pinfunction "2_2") (pintype "passive"))
      (node (ref "R50") (pin "1") (pinfunction "1_1") (pintype "passive"))
      (node (ref "R51") (pin "1") (pinfunction "1_1") (pintype "passive"))
      (node (ref "R52") (pin "1") (pinfunction "1_1") (pintype "passive"))
      (node (ref "R57") (pin "2") (pinfunction "2_2") (pintype "output"))
      (node (ref "U5") (pin "117") (pinfunction "VCCIO7_117") (pintype "power_in"))
      (node (ref "U5") (pin "122") (pinfunction "VCCIO7_122") (pintype "power_in"))
      (node (ref "U5") (pin "130") (pinfunction "VCCIO8_130") (pintype "power_in"))
      (node (ref "U5") (pin "139") (pinfunction "VCCIO8_139") (pintype "power_in"))
      (node (ref "U5") (pin "17") (pinfunction "VCCIO1_17") (pintype "power_in"))
      (node (ref "U5") (pin "26") (pinfunction "VCCIO2_26") (pintype "power_in"))
      (node (ref "U5") (pin "40") (pinfunction "VCCIO3_40") (pintype "power_in"))
      (node (ref "U5") (pin "47") (pinfunction "VCCIO3_47") (pintype "power_in"))
      (node (ref "U5") (pin "56") (pinfunction "VCCIO4_56") (pintype "power_in"))
      (node (ref "U5") (pin "62") (pinfunction "VCCIO4_62") (pintype "power_in"))
      (node (ref "U5") (pin "81") (pinfunction "VCCIO5_81") (pintype "power_in"))
      (node (ref "U5") (pin "93") (pinfunction "VCCIO6_93") (pintype "power_in"))
      (node (ref "U6") (pin "3") (pinfunction "VCC_3") (pintype "passive"))
      (node (ref "U6") (pin "7") (pinfunction "VCC_7") (pintype "passive"))
      (node (ref "U6") (pin "8") (pinfunction "VCC_8") (pintype "passive"))
      (node (ref "X1") (pin "1") (pinfunction "EN/NC_1") (pintype "passive"))
      (node (ref "X1") (pin "4") (pinfunction "VCC_4") (pintype "passive"))
    )
    (net (code "114") (name "Net-(E15-A)") (class "Default")
      (node (ref "E15") (pin "1") (pinfunction "A_1") (pintype "passive"))
      (node (ref "L4") (pin "2") (pinfunction "2_2") (pintype "passive"))
      (node (ref "U5") (pin "109") (pinfunction "VCCD_PLL2_109") (pintype "power_in"))
    )
    (net (code "115") (name "Net-(E16-A)") (class "Default")
      (node (ref "E16") (pin "1") (pinfunction "A_1") (pintype "passive"))
      (node (ref "L2") (pin "2") (pinfunction "2_2") (pintype "passive"))
      (node (ref "U5") (pin "37") (pinfunction "VCCD_PLL1_37") (pintype "power_in"))
    )
    (net (code "116") (name "Net-(U5J-CONF_DONE)") (class "Default")
      (node (ref "R50") (pin "2") (pinfunction "2_2") (pintype "output"))
      (node (ref "U5") (pin "92") (pinfunction "CONF_DONE_92") (pintype "bidirectional"))
    )
    (net (code "117") (name "Net-(U5J-nCONFIG)") (class "Default")
      (node (ref "R51") (pin "2") (pinfunction "2_2") (pintype "output"))
      (node (ref "U5") (pin "14") (pinfunction "nCONFIG_14") (pintype "input"))
    )
    (net (code "118") (name "Net-(U5J-nSTATUS)") (class "Default")
      (node (ref "R52") (pin "2") (pinfunction "2_2") (pintype "output"))
      (node (ref "U5") (pin "9") (pinfunction "nSTATUS_9") (pintype "bidirectional"))
    )
    (net (code "119") (name "Net-(U5M-GNDA1)") (class "Default")
      (node (ref "L1") (pin "1") (pinfunction "1_1") (pintype "passive"))
      (node (ref "U5") (pin "36") (pinfunction "GNDA1_36") (pintype "power_in"))
    )
    (net (code "120") (name "Net-(U5M-GNDA2)") (class "Default")
      (node (ref "L3") (pin "1") (pinfunction "1_1") (pintype "passive"))
      (node (ref "U5") (pin "108") (pinfunction "GNDA2_108") (pintype "power_in"))
    )
    (net (code "121") (name "Net-(U6-DATA)") (class "Default")
      (node (ref "R58") (pin "1") (pinfunction "1_1") (pintype "passive"))
      (node (ref "U6") (pin "2") (pinfunction "DATA_2") (pintype "passive"))
    )
    (net (code "122") (name "Net-(X1-OUT)") (class "Default")
      (node (ref "R53") (pin "1") (pinfunction "1_1") (pintype "passive"))
      (node (ref "X1") (pin "3") (pinfunction "OUT_3") (pintype "passive"))
    )
    (net (code "123") (name "unconnected-(JP2-Pad6)") (class "Default")
      (node (ref "JP2") (pin "6") (pinfunction "6_6") (pintype "passive"))
    )
    (net (code "124") (name "unconnected-(JP2-Pad7)") (class "Default")
      (node (ref "JP2") (pin "7") (pinfunction "7_7") (pintype "passive"))
    )
    (net (code "125") (name "unconnected-(JP2-Pad8)") (class "Default")
      (node (ref "JP2") (pin "8") (pinfunction "8_8") (pintype "passive"))
    )
    (net (code "126") (name "unconnected-(U5A-IO,_DIFFIO_L4n-Pad11)") (class "Default")
      (node (ref "U5") (pin "11") (pinfunction "IO,_DIFFIO_L4n_11") (pintype "bidirectional"))
    )
    (net (code "127") (name "unconnected-(U5I-CLK2,_DIFFCLK_1p-Pad24)") (class "Default")
      (node (ref "U5") (pin "24") (pinfunction "CLK2,_DIFFCLK_1p_24") (pintype "input+no_connect"))
    )
    (net (code "128") (name "unconnected-(U5I-CLK4,_DIFFCLK_2p-Pad91)") (class "Default")
      (node (ref "U5") (pin "91") (pinfunction "CLK4,_DIFFCLK_2p_91") (pintype "input+no_connect"))
    )
    (net (code "129") (name "unconnected-(U5I-CLK6,_DIFFCLK_3p-Pad89)") (class "Default")
      (node (ref "U5") (pin "89") (pinfunction "CLK6,_DIFFCLK_3p_89") (pintype "input+no_connect"))
    )
  )
)
